# Top_Design.net
KiCad netlist of a schematic drawn in Altium Designer
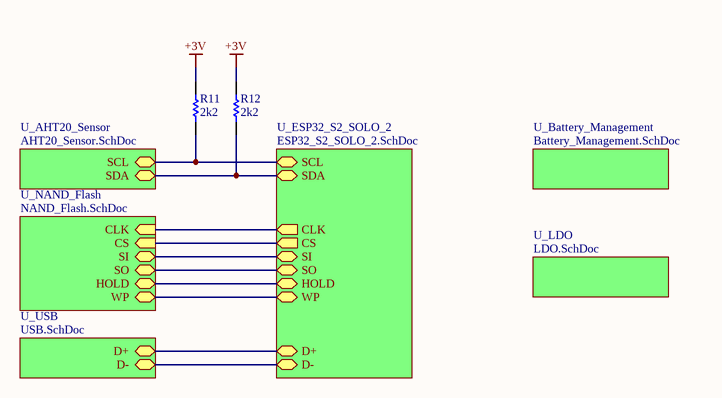
[diagram p0: Top_Design.SchDoc]

(export (version "E")
  (design (tool "Eeschema 10.0.6"))
  (components
    (comp (ref "R11")
      (value "2k2")
      (footprint "Wurth 0603 Resistor")
      (fields (field (name "Comment") "Generic Resistor 2k2 0603"))
      (libsource (lib "Passives") (part "Generic Resistor 2k2 0603"))
    )
    (comp (ref "R12")
      (value "2k2")
      (footprint "Wurth 0603 Resistor")
      (fields (field (name "Comment") "Generic Resistor 2k2 0603"))
      (libsource (lib "Passives") (part "Generic Resistor 2k2 0603"))
    )
  )
  (nets
    (net (code "1") (name "+3V") (class "Default")
      (node (ref "R11") (pin "2") (pinfunction "2_2") (pintype "passive"))
      (node (ref "R12") (pin "2") (pinfunction "2_2") (pintype "passive"))
    )
    (net (code "7") (name "/SCL") (class "Default")
      (node (ref "R11") (pin "1") (pinfunction "1_1") (pintype "passive"))
    )
    (net (code "8") (name "/SDA") (class "Default")
      (node (ref "R12") (pin "1") (pinfunction "1_1") (pintype "passive"))
    )
  )
)
